# Bank2.net
KiCad netlist of a schematic drawn in Altium Designer
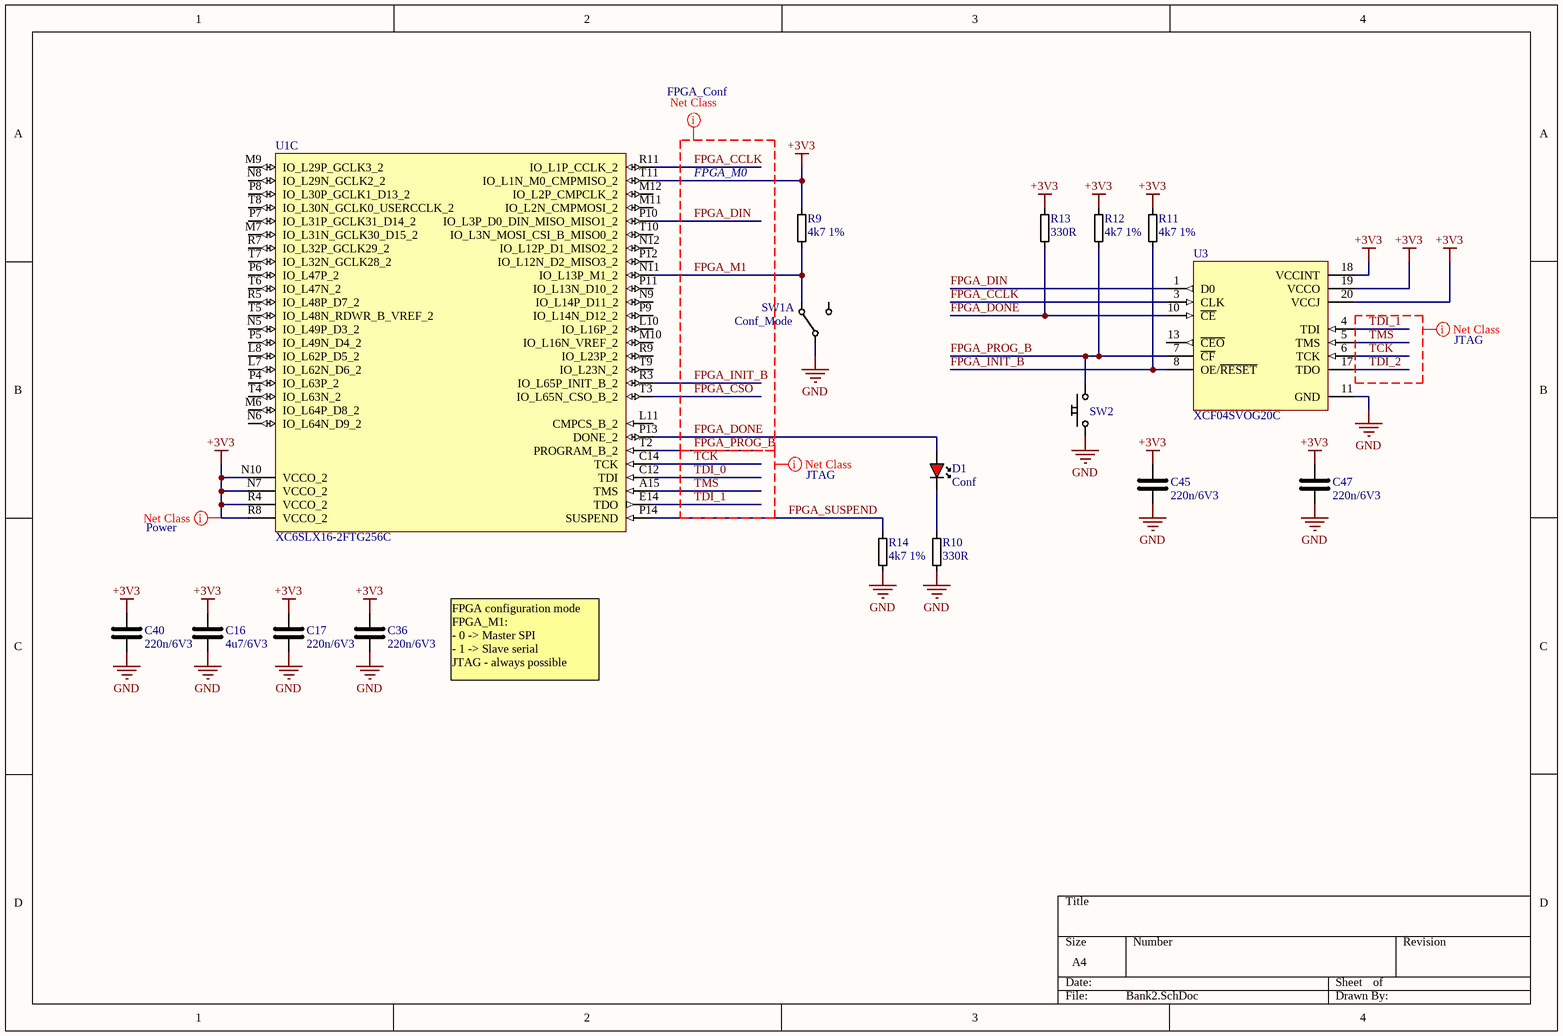
[diagram p0: Bank2.SchDoc]

(export (version "E")
  (design (tool "Eeschema 10.0.6"))
  (components
    (comp (ref "C16") (value "4u7/6V3") (footprint "C0805_N") (libsource (lib "niceCircuits") (part "C")))
    (comp (ref "C17") (value "220n/6V3") (footprint "C0402_N") (libsource (lib "niceCircuits") (part "C")))
    (comp (ref "C36") (value "220n/6V3") (footprint "C0402_N") (libsource (lib "niceCircuits") (part "C")))
    (comp (ref "C40") (value "220n/6V3") (footprint "C0402_N") (libsource (lib "niceCircuits") (part "C")))
    (comp (ref "C45") (value "220n/6V3") (footprint "C0402_N") (libsource (lib "niceCircuits") (part "C")))
    (comp (ref "C47") (value "220n/6V3") (footprint "C0402_N") (libsource (lib "niceCircuits") (part "C")))
    (comp (ref "D1")
      (value "Conf")
      (footprint "LED0603_red_N")
      (description "Generic 0603 Super Bright Red LED")
      (libsource (lib "niceCircuits") (part "LED_0603_Red_Super_Bright"))
    )
    (comp (ref "R9") (value "4k7 1%") (footprint "R0402_N") (libsource (lib "niceCircuits") (part "R")))
    (comp (ref "R10") (value "330R") (footprint "R0402_N") (libsource (lib "niceCircuits") (part "R")))
    (comp (ref "R11") (value "4k7 1%") (footprint "R0402_N") (libsource (lib "niceCircuits") (part "R")))
    (comp (ref "R12") (value "4k7 1%") (footprint "R0402_N") (libsource (lib "niceCircuits") (part "R")))
    (comp (ref "R13") (value "330R") (footprint "R0402_N") (libsource (lib "niceCircuits") (part "R")))
    (comp (ref "R14") (value "4k7 1%") (footprint "R0402_N") (libsource (lib "niceCircuits") (part "R")))
    (comp (ref "SW1")
      (value "Conf_Mode")
      (footprint "JS202011AQN")
      (libsource (lib "niceCircuits") (part "JS202011AQN"))
    )
    (comp (ref "SW2")
      (value "SW 4,3mm 1,5N SMD")
      (footprint "SW4,3SMD")
      (description "Microswitch 4,3mm")
      (libsource (lib "niceCircuits") (part "SW 4,3mm 1,5N SMD"))
    )
    (comp (ref "U1")
      (value "XC6SLX16-2FTG256C")
      (footprint "Xilinx_FT256")
      (libsource (lib "niceCircuits") (part "XC6SLX16-2FTG256C"))
    )
    (comp (ref "U3")
      (value "XCF04SVOG20C")
      (footprint "Xilinx_TSOP20_N")
      (description "Xilinx Platform Flash configuration memory 4Mbit")
      (libsource (lib "niceCircuits") (part "XCF04SVOG20C"))
    )
  )
  (nets
    (net (code "1") (name "+3V3") (class "Default")
      (node (ref "C16") (pin "2") (pinfunction "2_2") (pintype "passive"))
      (node (ref "C17") (pin "2") (pinfunction "2_2") (pintype "passive"))
      (node (ref "C36") (pin "2") (pinfunction "2_2") (pintype "passive"))
      (node (ref "C40") (pin "2") (pinfunction "2_2") (pintype "passive"))
      (node (ref "C45") (pin "2") (pinfunction "2_2") (pintype "passive"))
      (node (ref "C47") (pin "2") (pinfunction "2_2") (pintype "passive"))
      (node (ref "R11") (pin "1") (pinfunction "1_1") (pintype "passive"))
      (node (ref "R12") (pin "1") (pinfunction "1_1") (pintype "passive"))
      (node (ref "R13") (pin "1") (pinfunction "1_1") (pintype "passive"))
      (node (ref "R9") (pin "1") (pinfunction "1_1") (pintype "passive"))
      (node (ref "U1") (pin "N10") (pinfunction "VCCO_2_N10") (pintype "power_in"))
      (node (ref "U1") (pin "N7") (pinfunction "VCCO_2_N7") (pintype "power_in"))
      (node (ref "U1") (pin "R4") (pinfunction "VCCO_2_R4") (pintype "power_in"))
      (node (ref "U1") (pin "R8") (pinfunction "VCCO_2_R8") (pintype "power_in"))
      (node (ref "U1") (pin "T11") (pinfunction "IO_L1N_M0_CMPMISO_2_T11") (pintype "bidirectional"))
      (node (ref "U3") (pin "18") (pinfunction "VCCINT_18") (pintype "power_in"))
      (node (ref "U3") (pin "19") (pinfunction "VCCO_19") (pintype "power_in"))
      (node (ref "U3") (pin "20") (pinfunction "VCCJ_20") (pintype "power_in"))
    )
    (net (code "2") (name "/FPGA_CCLK") (class "Default")
      (node (ref "U1") (pin "R11") (pinfunction "IO_L1P_CCLK_2_R11") (pintype "bidirectional"))
      (node (ref "U3") (pin "3") (pinfunction "CLK_3") (pintype "input"))
    )
    (net (code "3") (name "/FPGA_CSO") (class "Default")
      (node (ref "U1") (pin "T3") (pinfunction "IO_L65N_CSO_B_2_T3") (pintype "bidirectional"))
    )
    (net (code "4") (name "/FPGA_DIN") (class "Default")
      (node (ref "U1") (pin "P10") (pinfunction "IO_L3P_D0_DIN_MISO_MISO1_2_P10") (pintype "bidirectional"))
      (node (ref "U3") (pin "1") (pinfunction "D0_1") (pintype "output"))
    )
    (net (code "5") (name "/FPGA_DONE") (class "Default")
      (node (ref "D1") (pin "1") (pinfunction "1_1") (pintype "passive"))
      (node (ref "R13") (pin "2") (pinfunction "2_2") (pintype "passive"))
      (node (ref "U1") (pin "P13") (pinfunction "DONE_2_P13") (pintype "bidirectional"))
      (node (ref "U3") (pin "10") (pinfunction "~{CE}_10") (pintype "input"))
    )
    (net (code "6") (name "/FPGA_INIT_B") (class "Default")
      (node (ref "R11") (pin "2") (pinfunction "2_2") (pintype "passive"))
      (node (ref "U1") (pin "R3") (pinfunction "IO_L65P_INIT_B_2_R3") (pintype "bidirectional"))
      (node (ref "U3") (pin "8") (pinfunction "OE/~{RESET}_8") (pintype "open_collector"))
    )
    (net (code "7") (name "/FPGA_M1") (class "Default")
      (node (ref "R9") (pin "2") (pinfunction "2_2") (pintype "passive"))
      (node (ref "SW1") (pin "NC1") (pinfunction "NC1_NC1") (pintype "passive"))
      (node (ref "U1") (pin "N11") (pinfunction "IO_L13P_M1_2_N11") (pintype "bidirectional"))
    )
    (net (code "8") (name "/FPGA_PROG_B") (class "Default")
      (node (ref "R12") (pin "2") (pinfunction "2_2") (pintype "passive"))
      (node (ref "SW2") (pin "2") (pinfunction "2_2") (pintype "passive"))
      (node (ref "U1") (pin "T2") (pinfunction "PROGRAM_B_2_T2") (pintype "input"))
      (node (ref "U3") (pin "7") (pinfunction "~{CF}_7") (pintype "open_collector"))
    )
    (net (code "9") (name "/FPGA_SUSPEND") (class "Default")
      (node (ref "R14") (pin "1") (pinfunction "1_1") (pintype "passive"))
      (node (ref "U1") (pin "P14") (pinfunction "SUSPEND_P14") (pintype "input"))
    )
    (net (code "10") (name "/TCK") (class "Default")
      (node (ref "U1") (pin "C14") (pinfunction "TCK_C14") (pintype "input"))
      (node (ref "U3") (pin "6") (pinfunction "TCK_6") (pintype "input"))
    )
    (net (code "11") (name "/TDI_0") (class "Default")
      (node (ref "U1") (pin "C12") (pinfunction "TDI_C12") (pintype "input"))
    )
    (net (code "12") (name "/TDI_1") (class "Default")
      (node (ref "U1") (pin "E14") (pinfunction "TDO_E14") (pintype "output"))
      (node (ref "U3") (pin "4") (pinfunction "TDI_4") (pintype "input"))
    )
    (net (code "13") (name "/TDI_2") (class "Default")
      (node (ref "U3") (pin "17") (pinfunction "TDO_17") (pintype "power_in"))
    )
    (net (code "14") (name "/TMS") (class "Default")
      (node (ref "U1") (pin "A15") (pinfunction "TMS_A15") (pintype "input"))
      (node (ref "U3") (pin "5") (pinfunction "TMS_5") (pintype "input"))
    )
    (net (code "15") (name "GND") (class "Default")
      (node (ref "C16") (pin "1") (pinfunction "1_1") (pintype "passive"))
      (node (ref "C17") (pin "1") (pinfunction "1_1") (pintype "passive"))
      (node (ref "C36") (pin "1") (pinfunction "1_1") (pintype "passive"))
      (node (ref "C40") (pin "1") (pinfunction "1_1") (pintype "passive"))
      (node (ref "C45") (pin "1") (pinfunction "1_1") (pintype "passive"))
      (node (ref "C47") (pin "1") (pinfunction "1_1") (pintype "passive"))
      (node (ref "R10") (pin "2") (pinfunction "2_2") (pintype "passive"))
      (node (ref "R14") (pin "2") (pinfunction "2_2") (pintype "passive"))
      (node (ref "SW1") (pin "COM1") (pinfunction "COM1_COM1") (pintype "passive"))
      (node (ref "SW2") (pin "1") (pinfunction "1_1") (pintype "passive"))
      (node (ref "U3") (pin "11") (pinfunction "GND_11") (pintype "power_in"))
    )
    (net (code "16") (name "Net-(D1-Pad2)") (class "Default")
      (node (ref "D1") (pin "2") (pinfunction "2_2") (pintype "passive"))
      (node (ref "R10") (pin "1") (pinfunction "1_1") (pintype "passive"))
    )
    (net (code "17") (name "unconnected-(SW1-PadNO1)") (class "Default")
      (node (ref "SW1") (pin "NO1") (pinfunction "NO1_NO1") (pintype "passive"))
    )
    (net (code "18") (name "unconnected-(U1C-CMPCS_B_2-PadL11)") (class "Default")
      (node (ref "U1") (pin "L11") (pinfunction "CMPCS_B_2_L11") (pintype "input"))
    )
    (net (code "19") (name "unconnected-(U1C-IO_L2N_CMPMOSI_2-PadM11)") (class "Default")
      (node (ref "U1") (pin "M11") (pinfunction "IO_L2N_CMPMOSI_2_M11") (pintype "bidirectional"))
    )
    (net (code "20") (name "unconnected-(U1C-IO_L2P_CMPCLK_2-PadM12)") (class "Default")
      (node (ref "U1") (pin "M12") (pinfunction "IO_L2P_CMPCLK_2_M12") (pintype "bidirectional"))
    )
    (net (code "21") (name "unconnected-(U1C-IO_L3N_MOSI_CSI_B_MISO0_2-PadT10)") (class "Default")
      (node (ref "U1") (pin "T10") (pinfunction "IO_L3N_MOSI_CSI_B_MISO0_2_T10") (pintype "bidirectional"))
    )
    (net (code "22") (name "unconnected-(U1C-IO_L12N_D2_MISO3_2-PadP12)") (class "Default")
      (node (ref "U1") (pin "P12") (pinfunction "IO_L12N_D2_MISO3_2_P12") (pintype "bidirectional"))
    )
    (net (code "23") (name "unconnected-(U1C-IO_L12P_D1_MISO2_2-PadN12)") (class "Default")
      (node (ref "U1") (pin "N12") (pinfunction "IO_L12P_D1_MISO2_2_N12") (pintype "bidirectional"))
    )
    (net (code "24") (name "unconnected-(U1C-IO_L13N_D10_2-PadP11)") (class "Default")
      (node (ref "U1") (pin "P11") (pinfunction "IO_L13N_D10_2_P11") (pintype "bidirectional"))
    )
    (net (code "25") (name "unconnected-(U1C-IO_L14N_D12_2-PadP9)") (class "Default")
      (node (ref "U1") (pin "P9") (pinfunction "IO_L14N_D12_2_P9") (pintype "bidirectional"))
    )
    (net (code "26") (name "unconnected-(U1C-IO_L14P_D11_2-PadN9)") (class "Default")
      (node (ref "U1") (pin "N9") (pinfunction "IO_L14P_D11_2_N9") (pintype "bidirectional"))
    )
    (net (code "27") (name "unconnected-(U1C-IO_L16N_VREF_2-PadM10)") (class "Default")
      (node (ref "U1") (pin "M10") (pinfunction "IO_L16N_VREF_2_M10") (pintype "bidirectional"))
    )
    (net (code "28") (name "unconnected-(U1C-IO_L16P_2-PadL10)") (class "Default")
      (node (ref "U1") (pin "L10") (pinfunction "IO_L16P_2_L10") (pintype "bidirectional"))
    )
    (net (code "29") (name "unconnected-(U1C-IO_L23N_2-PadT9)") (class "Default")
      (node (ref "U1") (pin "T9") (pinfunction "IO_L23N_2_T9") (pintype "bidirectional"))
    )
    (net (code "30") (name "unconnected-(U1C-IO_L23P_2-PadR9)") (class "Default")
      (node (ref "U1") (pin "R9") (pinfunction "IO_L23P_2_R9") (pintype "bidirectional"))
    )
    (net (code "31") (name "unconnected-(U1C-IO_L29N_GCLK2_2-PadN8)") (class "Default")
      (node (ref "U1") (pin "N8") (pinfunction "IO_L29N_GCLK2_2_N8") (pintype "bidirectional"))
    )
    (net (code "32") (name "unconnected-(U1C-IO_L29P_GCLK3_2-PadM9)") (class "Default")
      (node (ref "U1") (pin "M9") (pinfunction "IO_L29P_GCLK3_2_M9") (pintype "bidirectional"))
    )
    (net (code "33") (name "unconnected-(U1C-IO_L30N_GCLK0_USERCCLK_2-PadT8)") (class "Default")
      (node (ref "U1") (pin "T8") (pinfunction "IO_L30N_GCLK0_USERCCLK_2_T8") (pintype "bidirectional"))
    )
    (net (code "34") (name "unconnected-(U1C-IO_L30P_GCLK1_D13_2-PadP8)") (class "Default")
      (node (ref "U1") (pin "P8") (pinfunction "IO_L30P_GCLK1_D13_2_P8") (pintype "bidirectional"))
    )
    (net (code "35") (name "unconnected-(U1C-IO_L31N_GCLK30_D15_2-PadM7)") (class "Default")
      (node (ref "U1") (pin "M7") (pinfunction "IO_L31N_GCLK30_D15_2_M7") (pintype "bidirectional"))
    )
    (net (code "36") (name "unconnected-(U1C-IO_L31P_GCLK31_D14_2-PadP7)") (class "Default")
      (node (ref "U1") (pin "P7") (pinfunction "IO_L31P_GCLK31_D14_2_P7") (pintype "bidirectional"))
    )
    (net (code "37") (name "unconnected-(U1C-IO_L32N_GCLK28_2-PadT7)") (class "Default")
      (node (ref "U1") (pin "T7") (pinfunction "IO_L32N_GCLK28_2_T7") (pintype "bidirectional"))
    )
    (net (code "38") (name "unconnected-(U1C-IO_L32P_GCLK29_2-PadR7)") (class "Default")
      (node (ref "U1") (pin "R7") (pinfunction "IO_L32P_GCLK29_2_R7") (pintype "bidirectional"))
    )
    (net (code "39") (name "unconnected-(U1C-IO_L47N_2-PadT6)") (class "Default")
      (node (ref "U1") (pin "T6") (pinfunction "IO_L47N_2_T6") (pintype "bidirectional"))
    )
    (net (code "40") (name "unconnected-(U1C-IO_L47P_2-PadP6)") (class "Default")
      (node (ref "U1") (pin "P6") (pinfunction "IO_L47P_2_P6") (pintype "bidirectional"))
    )
    (net (code "41") (name "unconnected-(U1C-IO_L48N_RDWR_B_VREF_2-PadT5)") (class "Default")
      (node (ref "U1") (pin "T5") (pinfunction "IO_L48N_RDWR_B_VREF_2_T5") (pintype "bidirectional"))
    )
    (net (code "42") (name "unconnected-(U1C-IO_L48P_D7_2-PadR5)") (class "Default")
      (node (ref "U1") (pin "R5") (pinfunction "IO_L48P_D7_2_R5") (pintype "bidirectional"))
    )
    (net (code "43") (name "unconnected-(U1C-IO_L49N_D4_2-PadP5)") (class "Default")
      (node (ref "U1") (pin "P5") (pinfunction "IO_L49N_D4_2_P5") (pintype "bidirectional"))
    )
    (net (code "44") (name "unconnected-(U1C-IO_L49P_D3_2-PadN5)") (class "Default")
      (node (ref "U1") (pin "N5") (pinfunction "IO_L49P_D3_2_N5") (pintype "bidirectional"))
    )
    (net (code "45") (name "unconnected-(U1C-IO_L62N_D6_2-PadL7)") (class "Default")
      (node (ref "U1") (pin "L7") (pinfunction "IO_L62N_D6_2_L7") (pintype "bidirectional"))
    )
    (net (code "46") (name "unconnected-(U1C-IO_L62P_D5_2-PadL8)") (class "Default")
      (node (ref "U1") (pin "L8") (pinfunction "IO_L62P_D5_2_L8") (pintype "bidirectional"))
    )
    (net (code "47") (name "unconnected-(U1C-IO_L63N_2-PadT4)") (class "Default")
      (node (ref "U1") (pin "T4") (pinfunction "IO_L63N_2_T4") (pintype "bidirectional"))
    )
    (net (code "48") (name "unconnected-(U1C-IO_L63P_2-PadP4)") (class "Default")
      (node (ref "U1") (pin "P4") (pinfunction "IO_L63P_2_P4") (pintype "bidirectional"))
    )
    (net (code "49") (name "unconnected-(U1C-IO_L64N_D9_2-PadN6)") (class "Default")
      (node (ref "U1") (pin "N6") (pinfunction "IO_L64N_D9_2_N6") (pintype "bidirectional"))
    )
    (net (code "50") (name "unconnected-(U1C-IO_L64P_D8_2-PadM6)") (class "Default")
      (node (ref "U1") (pin "M6") (pinfunction "IO_L64P_D8_2_M6") (pintype "bidirectional"))
    )
    (net (code "51") (name "unconnected-(U3-~{CEO}-Pad13)") (class "Default")
      (node (ref "U3") (pin "13") (pinfunction "~{CEO}_13") (pintype "output"))
    )
  )
)
